# msp432_breakout_uart.net
KiCad netlist of a schematic drawn in EAGLE
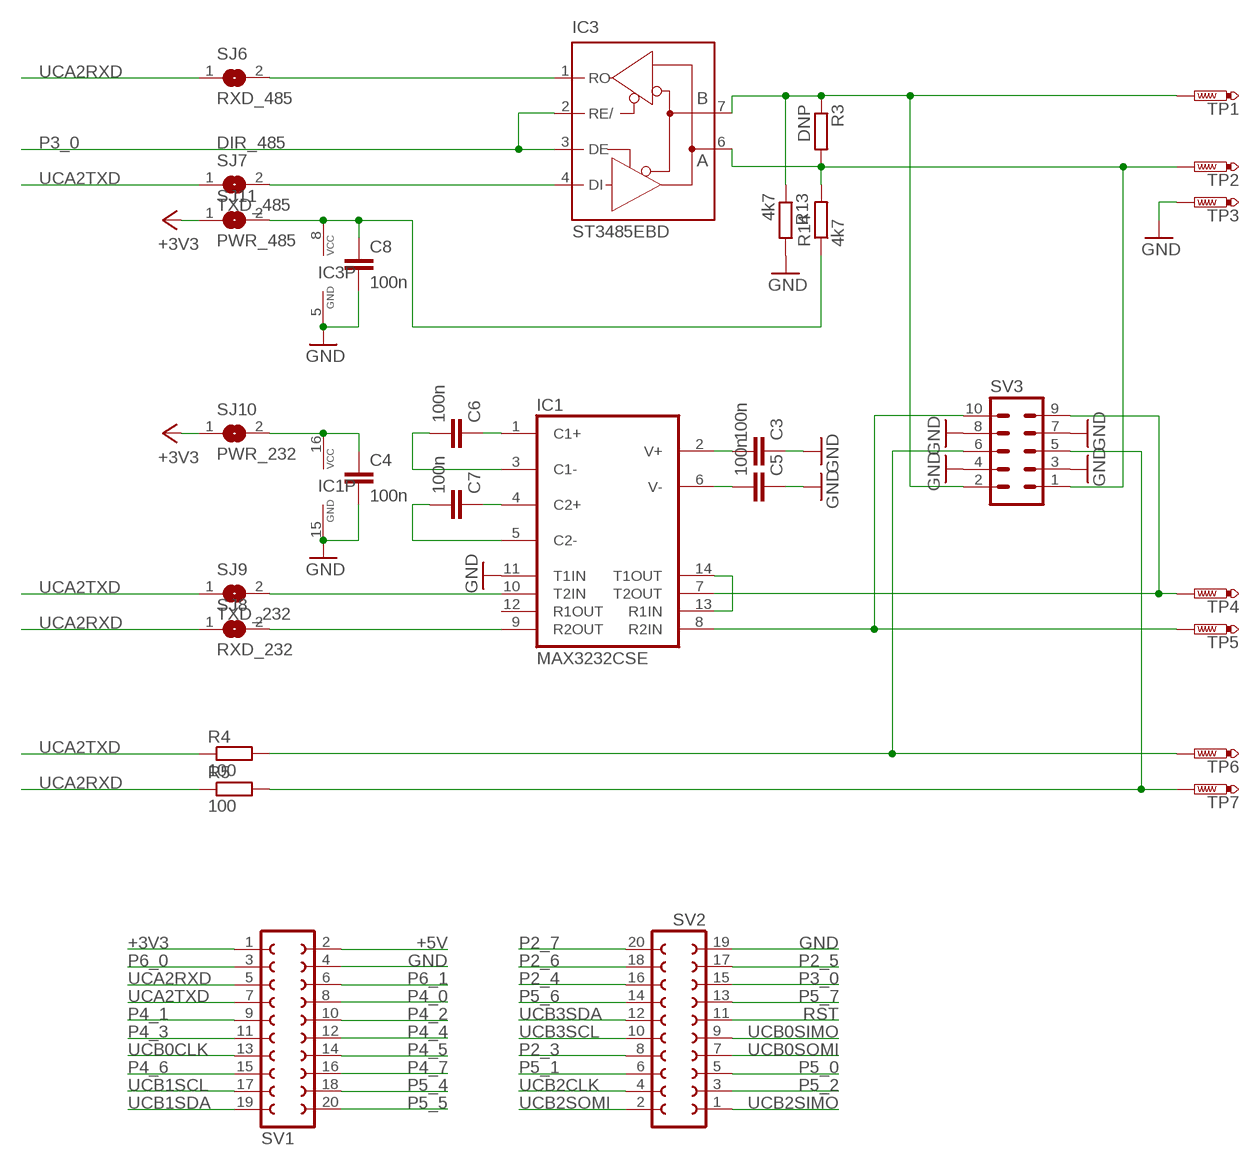
[diagram p0: schematic, sheet 1]

(export (version "E")
  (design (tool "Eeschema 10.0.6"))
  (components
    (comp (ref "C3")
      (value "100n")
      (footprint "eagle-import:C0603")
      (libsource (lib "eagle-import") (part "C-EUC0603"))
    )
    (comp (ref "C4")
      (value "100n")
      (footprint "eagle-import:C0603")
      (libsource (lib "eagle-import") (part "C-EUC0603"))
    )
    (comp (ref "C5")
      (value "100n")
      (footprint "eagle-import:C0603")
      (libsource (lib "eagle-import") (part "C-EUC0603"))
    )
    (comp (ref "C6")
      (value "100n")
      (footprint "eagle-import:C0603")
      (libsource (lib "eagle-import") (part "C-EUC0603"))
    )
    (comp (ref "C7")
      (value "100n")
      (footprint "eagle-import:C0603")
      (libsource (lib "eagle-import") (part "C-EUC0603"))
    )
    (comp (ref "C8")
      (value "100n")
      (footprint "eagle-import:C0603")
      (libsource (lib "eagle-import") (part "C-EUC0603"))
    )
    (comp (ref "IC1")
      (value "MAX3232CSE")
      (footprint "eagle-import:SO16")
      (libsource (lib "eagle-import") (part "MAX3232SEC"))
    )
    (comp (ref "IC3")
      (value "ST3485EBD")
      (footprint "eagle-import:SO08")
      (fields (field (name "MF") "MAXIM") (field (name "MPN") "MAX481CSA"))
      (libsource (lib "eagle-import") (part "MAX481CSA"))
    )
    (comp (ref "R3")
      (value "DNP")
      (footprint "eagle-import:R0603")
      (libsource (lib "eagle-import") (part "R-EU_R0603"))
    )
    (comp (ref "R4")
      (value "100")
      (footprint "eagle-import:R0603")
      (libsource (lib "eagle-import") (part "R-EU_R0603"))
    )
    (comp (ref "R5")
      (value "100")
      (footprint "eagle-import:R0603")
      (libsource (lib "eagle-import") (part "R-EU_R0603"))
    )
    (comp (ref "R13")
      (value "4k7")
      (footprint "eagle-import:R0603")
      (libsource (lib "eagle-import") (part "R-EU_R0603"))
    )
    (comp (ref "R14")
      (value "4k7")
      (footprint "eagle-import:R0603")
      (libsource (lib "eagle-import") (part "R-EU_R0603"))
    )
    (comp (ref "SJ6")
      (value "RXD_485")
      (footprint "eagle-import:SJ")
      (libsource (lib "eagle-import") (part "SJ"))
    )
    (comp (ref "SJ7")
      (value "TXD_485")
      (footprint "eagle-import:SJ")
      (libsource (lib "eagle-import") (part "SJ"))
    )
    (comp (ref "SJ8")
      (value "RXD_232")
      (footprint "eagle-import:SJ")
      (libsource (lib "eagle-import") (part "SJ"))
    )
    (comp (ref "SJ9")
      (value "TXD_232")
      (footprint "eagle-import:SJ")
      (libsource (lib "eagle-import") (part "SJ"))
    )
    (comp (ref "SJ10")
      (value "PWR_232")
      (footprint "eagle-import:SJ")
      (libsource (lib "eagle-import") (part "SJ"))
    )
    (comp (ref "SJ11")
      (value "PWR_485")
      (footprint "eagle-import:SJ")
      (libsource (lib "eagle-import") (part "SJ"))
    )
    (comp (ref "SV1")
      (value "FE10-2")
      (footprint "eagle-import:FE10-2")
      (libsource (lib "eagle-import") (part "FE10-2"))
    )
    (comp (ref "SV2")
      (value "FE10-2")
      (footprint "eagle-import:FE10-2")
      (libsource (lib "eagle-import") (part "FE10-2"))
    )
    (comp (ref "SV3")
      (value "ML10")
      (footprint "eagle-import:ML10")
      (libsource (lib "eagle-import") (part "ML10"))
    )
    (comp (ref "TP1")
      (value "PTR1PAD1-20")
      (footprint "eagle-import:P1-20")
      (libsource (lib "eagle-import") (part "PTR1PAD1-20"))
    )
    (comp (ref "TP2")
      (value "PTR1PAD1-20")
      (footprint "eagle-import:P1-20")
      (libsource (lib "eagle-import") (part "PTR1PAD1-20"))
    )
    (comp (ref "TP3")
      (value "PTR1PAD1-20")
      (footprint "eagle-import:P1-20")
      (libsource (lib "eagle-import") (part "PTR1PAD1-20"))
    )
    (comp (ref "TP4")
      (value "PTR1PAD1-20")
      (footprint "eagle-import:P1-20")
      (libsource (lib "eagle-import") (part "PTR1PAD1-20"))
    )
    (comp (ref "TP5")
      (value "PTR1PAD1-20")
      (footprint "eagle-import:P1-20")
      (libsource (lib "eagle-import") (part "PTR1PAD1-20"))
    )
    (comp (ref "TP6")
      (value "PTR1PAD1-20")
      (footprint "eagle-import:P1-20")
      (libsource (lib "eagle-import") (part "PTR1PAD1-20"))
    )
    (comp (ref "TP7")
      (value "PTR1PAD1-20")
      (footprint "eagle-import:P1-20")
      (libsource (lib "eagle-import") (part "PTR1PAD1-20"))
    )
  )
  (nets
    (net (code "1") (name "+3V3") (class "Default")
      (node (ref "SJ10") (pin "1") (pinfunction "1_1") (pintype "passive"))
      (node (ref "SJ11") (pin "1") (pinfunction "1_1") (pintype "passive"))
      (node (ref "SV1") (pin "1") (pinfunction "1_1") (pintype "passive"))
    )
    (net (code "2") (name "/+5V") (class "Default")
      (node (ref "SV1") (pin "2") (pinfunction "2_2") (pintype "passive"))
    )
    (net (code "3") (name "/P2_3") (class "Default")
      (node (ref "SV2") (pin "8") (pinfunction "8_8") (pintype "passive"))
    )
    (net (code "4") (name "/P2_4") (class "Default")
      (node (ref "SV2") (pin "16") (pinfunction "16_16") (pintype "passive"))
    )
    (net (code "5") (name "/P2_5") (class "Default")
      (node (ref "SV2") (pin "17") (pinfunction "17_17") (pintype "passive"))
    )
    (net (code "6") (name "/P2_6") (class "Default")
      (node (ref "SV2") (pin "18") (pinfunction "18_18") (pintype "passive"))
    )
    (net (code "7") (name "/P2_7") (class "Default")
      (node (ref "SV2") (pin "20") (pinfunction "20_20") (pintype "passive"))
    )
    (net (code "8") (name "/P3_0") (class "Default")
      (node (ref "IC3") (pin "2") (pinfunction "RE/_2") (pintype "input"))
      (node (ref "IC3") (pin "3") (pinfunction "DE_3") (pintype "input"))
      (node (ref "SV2") (pin "15") (pinfunction "15_15") (pintype "passive"))
    )
    (net (code "9") (name "/P4_0") (class "Default")
      (node (ref "SV1") (pin "8") (pinfunction "8_8") (pintype "passive"))
    )
    (net (code "10") (name "/P4_1") (class "Default")
      (node (ref "SV1") (pin "9") (pinfunction "9_9") (pintype "passive"))
    )
    (net (code "11") (name "/P4_2") (class "Default")
      (node (ref "SV1") (pin "10") (pinfunction "10_10") (pintype "passive"))
    )
    (net (code "12") (name "/P4_3") (class "Default")
      (node (ref "SV1") (pin "11") (pinfunction "11_11") (pintype "passive"))
    )
    (net (code "13") (name "/P4_4") (class "Default")
      (node (ref "SV1") (pin "12") (pinfunction "12_12") (pintype "passive"))
    )
    (net (code "14") (name "/P4_5") (class "Default")
      (node (ref "SV1") (pin "14") (pinfunction "14_14") (pintype "passive"))
    )
    (net (code "15") (name "/P4_6") (class "Default")
      (node (ref "SV1") (pin "15") (pinfunction "15_15") (pintype "passive"))
    )
    (net (code "16") (name "/P4_7") (class "Default")
      (node (ref "SV1") (pin "16") (pinfunction "16_16") (pintype "passive"))
    )
    (net (code "17") (name "/P5_0") (class "Default")
      (node (ref "SV2") (pin "5") (pinfunction "5_5") (pintype "passive"))
    )
    (net (code "18") (name "/P5_1") (class "Default")
      (node (ref "SV2") (pin "6") (pinfunction "6_6") (pintype "passive"))
    )
    (net (code "19") (name "/P5_2") (class "Default")
      (node (ref "SV2") (pin "3") (pinfunction "3_3") (pintype "passive"))
    )
    (net (code "20") (name "/P5_4") (class "Default")
      (node (ref "SV1") (pin "18") (pinfunction "18_18") (pintype "passive"))
    )
    (net (code "21") (name "/P5_5") (class "Default")
      (node (ref "SV1") (pin "20") (pinfunction "20_20") (pintype "passive"))
    )
    (net (code "22") (name "/P5_6") (class "Default")
      (node (ref "SV2") (pin "14") (pinfunction "14_14") (pintype "passive"))
    )
    (net (code "23") (name "/P5_7") (class "Default")
      (node (ref "SV2") (pin "13") (pinfunction "13_13") (pintype "passive"))
    )
    (net (code "24") (name "/P6_0") (class "Default")
      (node (ref "SV1") (pin "3") (pinfunction "3_3") (pintype "passive"))
    )
    (net (code "25") (name "/P6_1") (class "Default")
      (node (ref "SV1") (pin "6") (pinfunction "6_6") (pintype "passive"))
    )
    (net (code "26") (name "/RST") (class "Default")
      (node (ref "SV2") (pin "11") (pinfunction "11_11") (pintype "passive"))
    )
    (net (code "27") (name "/UCA2RXD") (class "Default")
      (node (ref "R5") (pin "1") (pinfunction "1_1") (pintype "passive"))
      (node (ref "SJ6") (pin "1") (pinfunction "1_1") (pintype "passive"))
      (node (ref "SJ8") (pin "1") (pinfunction "1_1") (pintype "passive"))
      (node (ref "SV1") (pin "5") (pinfunction "5_5") (pintype "passive"))
    )
    (net (code "28") (name "/UCA2TXD") (class "Default")
      (node (ref "R4") (pin "1") (pinfunction "1_1") (pintype "passive"))
      (node (ref "SJ7") (pin "1") (pinfunction "1_1") (pintype "passive"))
      (node (ref "SJ9") (pin "1") (pinfunction "1_1") (pintype "passive"))
      (node (ref "SV1") (pin "7") (pinfunction "7_7") (pintype "passive"))
    )
    (net (code "29") (name "/UCB0CLK") (class "Default")
      (node (ref "SV1") (pin "13") (pinfunction "13_13") (pintype "passive"))
    )
    (net (code "30") (name "/UCB0SIMO") (class "Default")
      (node (ref "SV2") (pin "9") (pinfunction "9_9") (pintype "passive"))
    )
    (net (code "31") (name "/UCB0SOMI") (class "Default")
      (node (ref "SV2") (pin "7") (pinfunction "7_7") (pintype "passive"))
    )
    (net (code "32") (name "/UCB1SCL") (class "Default")
      (node (ref "SV1") (pin "17") (pinfunction "17_17") (pintype "passive"))
    )
    (net (code "33") (name "/UCB1SDA") (class "Default")
      (node (ref "SV1") (pin "19") (pinfunction "19_19") (pintype "passive"))
    )
    (net (code "34") (name "/UCB2CLK") (class "Default")
      (node (ref "SV2") (pin "4") (pinfunction "4_4") (pintype "passive"))
    )
    (net (code "35") (name "/UCB2SIMO") (class "Default")
      (node (ref "SV2") (pin "1") (pinfunction "1_1") (pintype "passive"))
    )
    (net (code "36") (name "/UCB2SOMI") (class "Default")
      (node (ref "SV2") (pin "2") (pinfunction "2_2") (pintype "passive"))
    )
    (net (code "37") (name "/UCB3SCL") (class "Default")
      (node (ref "SV2") (pin "10") (pinfunction "10_10") (pintype "passive"))
    )
    (net (code "38") (name "/UCB3SDA") (class "Default")
      (node (ref "SV2") (pin "12") (pinfunction "12_12") (pintype "passive"))
    )
    (net (code "39") (name "GND") (class "Default")
      (node (ref "C3") (pin "1") (pinfunction "1_1") (pintype "passive"))
      (node (ref "C4") (pin "2") (pinfunction "2_2") (pintype "passive"))
      (node (ref "C5") (pin "1") (pinfunction "1_1") (pintype "passive"))
      (node (ref "C8") (pin "2") (pinfunction "2_2") (pintype "passive"))
      (node (ref "IC1") (pin "11") (pinfunction "T1IN_11") (pintype "input"))
      (node (ref "IC1") (pin "15") (pinfunction "GND_15") (pintype "power_in"))
      (node (ref "IC3") (pin "5") (pinfunction "GND_5") (pintype "power_in"))
      (node (ref "R13") (pin "2") (pinfunction "2_2") (pintype "passive"))
      (node (ref "SV1") (pin "4") (pinfunction "4_4") (pintype "passive"))
      (node (ref "SV2") (pin "19") (pinfunction "19_19") (pintype "passive"))
      (node (ref "SV3") (pin "3") (pinfunction "3_3") (pintype "passive"))
      (node (ref "SV3") (pin "4") (pinfunction "4_4") (pintype "passive"))
      (node (ref "SV3") (pin "7") (pinfunction "7_7") (pintype "passive"))
      (node (ref "SV3") (pin "8") (pinfunction "8_8") (pintype "passive"))
      (node (ref "TP3") (pin "TP") (pinfunction "TP_TP") (pintype "input"))
    )
    (net (code "40") (name "Net-(IC1A-C1+)") (class "Default")
      (node (ref "C6") (pin "1") (pinfunction "1_1") (pintype "passive"))
      (node (ref "IC1") (pin "1") (pinfunction "C1+_1") (pintype "bidirectional"))
    )
    (net (code "41") (name "Net-(IC1A-C1-)") (class "Default")
      (node (ref "C6") (pin "2") (pinfunction "2_2") (pintype "passive"))
      (node (ref "IC1") (pin "3") (pinfunction "C1-_3") (pintype "bidirectional"))
    )
    (net (code "42") (name "Net-(IC1A-C2+)") (class "Default")
      (node (ref "C7") (pin "1") (pinfunction "1_1") (pintype "passive"))
      (node (ref "IC1") (pin "4") (pinfunction "C2+_4") (pintype "bidirectional"))
    )
    (net (code "43") (name "Net-(IC1A-C2-)") (class "Default")
      (node (ref "C7") (pin "2") (pinfunction "2_2") (pintype "passive"))
      (node (ref "IC1") (pin "5") (pinfunction "C2-_5") (pintype "bidirectional"))
    )
    (net (code "44") (name "Net-(IC1A-R1IN)") (class "Default")
      (node (ref "IC1") (pin "13") (pinfunction "R1IN_13") (pintype "input"))
      (node (ref "IC1") (pin "14") (pinfunction "T1OUT_14") (pintype "output"))
    )
    (net (code "45") (name "Net-(IC1A-R2IN)") (class "Default")
      (node (ref "IC1") (pin "8") (pinfunction "R2IN_8") (pintype "input"))
      (node (ref "SV3") (pin "10") (pinfunction "10_10") (pintype "passive"))
      (node (ref "TP5") (pin "TP") (pinfunction "TP_TP") (pintype "input"))
    )
    (net (code "46") (name "Net-(IC1A-R2OUT)") (class "Default")
      (node (ref "IC1") (pin "9") (pinfunction "R2OUT_9") (pintype "output"))
      (node (ref "SJ8") (pin "2") (pinfunction "2_2") (pintype "passive"))
    )
    (net (code "47") (name "Net-(IC1A-T2IN)") (class "Default")
      (node (ref "IC1") (pin "10") (pinfunction "T2IN_10") (pintype "input"))
      (node (ref "SJ9") (pin "2") (pinfunction "2_2") (pintype "passive"))
    )
    (net (code "48") (name "Net-(IC1A-T2OUT)") (class "Default")
      (node (ref "IC1") (pin "7") (pinfunction "T2OUT_7") (pintype "output"))
      (node (ref "SV3") (pin "9") (pinfunction "9_9") (pintype "passive"))
      (node (ref "TP4") (pin "TP") (pinfunction "TP_TP") (pintype "input"))
    )
    (net (code "49") (name "Net-(IC1A-V+)") (class "Default")
      (node (ref "C3") (pin "2") (pinfunction "2_2") (pintype "passive"))
      (node (ref "IC1") (pin "2") (pinfunction "V+_2") (pintype "bidirectional"))
    )
    (net (code "50") (name "Net-(IC1A-V-)") (class "Default")
      (node (ref "C5") (pin "2") (pinfunction "2_2") (pintype "passive"))
      (node (ref "IC1") (pin "6") (pinfunction "V-_6") (pintype "bidirectional"))
    )
    (net (code "51") (name "Net-(IC1B-VCC)") (class "Default")
      (node (ref "C4") (pin "1") (pinfunction "1_1") (pintype "passive"))
      (node (ref "IC1") (pin "16") (pinfunction "VCC_16") (pintype "power_in"))
      (node (ref "SJ10") (pin "2") (pinfunction "2_2") (pintype "passive"))
    )
    (net (code "52") (name "Net-(IC3A-A)") (class "Default")
      (node (ref "IC3") (pin "6") (pinfunction "A_6") (pintype "passive"))
      (node (ref "R14") (pin "2") (pinfunction "2_2") (pintype "passive"))
      (node (ref "R3") (pin "2") (pinfunction "2_2") (pintype "passive"))
      (node (ref "SV3") (pin "1") (pinfunction "1_1") (pintype "passive"))
      (node (ref "TP2") (pin "TP") (pinfunction "TP_TP") (pintype "input"))
    )
    (net (code "53") (name "Net-(IC3A-B)") (class "Default")
      (node (ref "IC3") (pin "7") (pinfunction "B_7") (pintype "passive"))
      (node (ref "R13") (pin "1") (pinfunction "1_1") (pintype "passive"))
      (node (ref "R3") (pin "1") (pinfunction "1_1") (pintype "passive"))
      (node (ref "SV3") (pin "2") (pinfunction "2_2") (pintype "passive"))
      (node (ref "TP1") (pin "TP") (pinfunction "TP_TP") (pintype "input"))
    )
    (net (code "54") (name "Net-(IC3A-DI)") (class "Default")
      (node (ref "IC3") (pin "4") (pinfunction "DI_4") (pintype "input"))
      (node (ref "SJ7") (pin "2") (pinfunction "2_2") (pintype "passive"))
    )
    (net (code "55") (name "Net-(IC3A-RO)") (class "Default")
      (node (ref "IC3") (pin "1") (pinfunction "RO_1") (pintype "output"))
      (node (ref "SJ6") (pin "2") (pinfunction "2_2") (pintype "passive"))
    )
    (net (code "56") (name "Net-(IC3B-VCC)") (class "Default")
      (node (ref "C8") (pin "1") (pinfunction "1_1") (pintype "passive"))
      (node (ref "IC3") (pin "8") (pinfunction "VCC_8") (pintype "power_in"))
      (node (ref "R14") (pin "1") (pinfunction "1_1") (pintype "passive"))
      (node (ref "SJ11") (pin "2") (pinfunction "2_2") (pintype "passive"))
    )
    (net (code "57") (name "Net-(R4-Pad2)") (class "Default")
      (node (ref "R4") (pin "2") (pinfunction "2_2") (pintype "passive"))
      (node (ref "SV3") (pin "6") (pinfunction "6_6") (pintype "passive"))
      (node (ref "TP6") (pin "TP") (pinfunction "TP_TP") (pintype "input"))
    )
    (net (code "58") (name "Net-(R5-Pad2)") (class "Default")
      (node (ref "R5") (pin "2") (pinfunction "2_2") (pintype "passive"))
      (node (ref "SV3") (pin "5") (pinfunction "5_5") (pintype "passive"))
      (node (ref "TP7") (pin "TP") (pinfunction "TP_TP") (pintype "input"))
    )
    (net (code "59") (name "unconnected-(IC1A-R1OUT-Pad12)") (class "Default")
      (node (ref "IC1") (pin "12") (pinfunction "R1OUT_12") (pintype "output"))
    )
  )
)
